# pneu-sensor.net
KiCad netlist of a schematic drawn in EAGLE
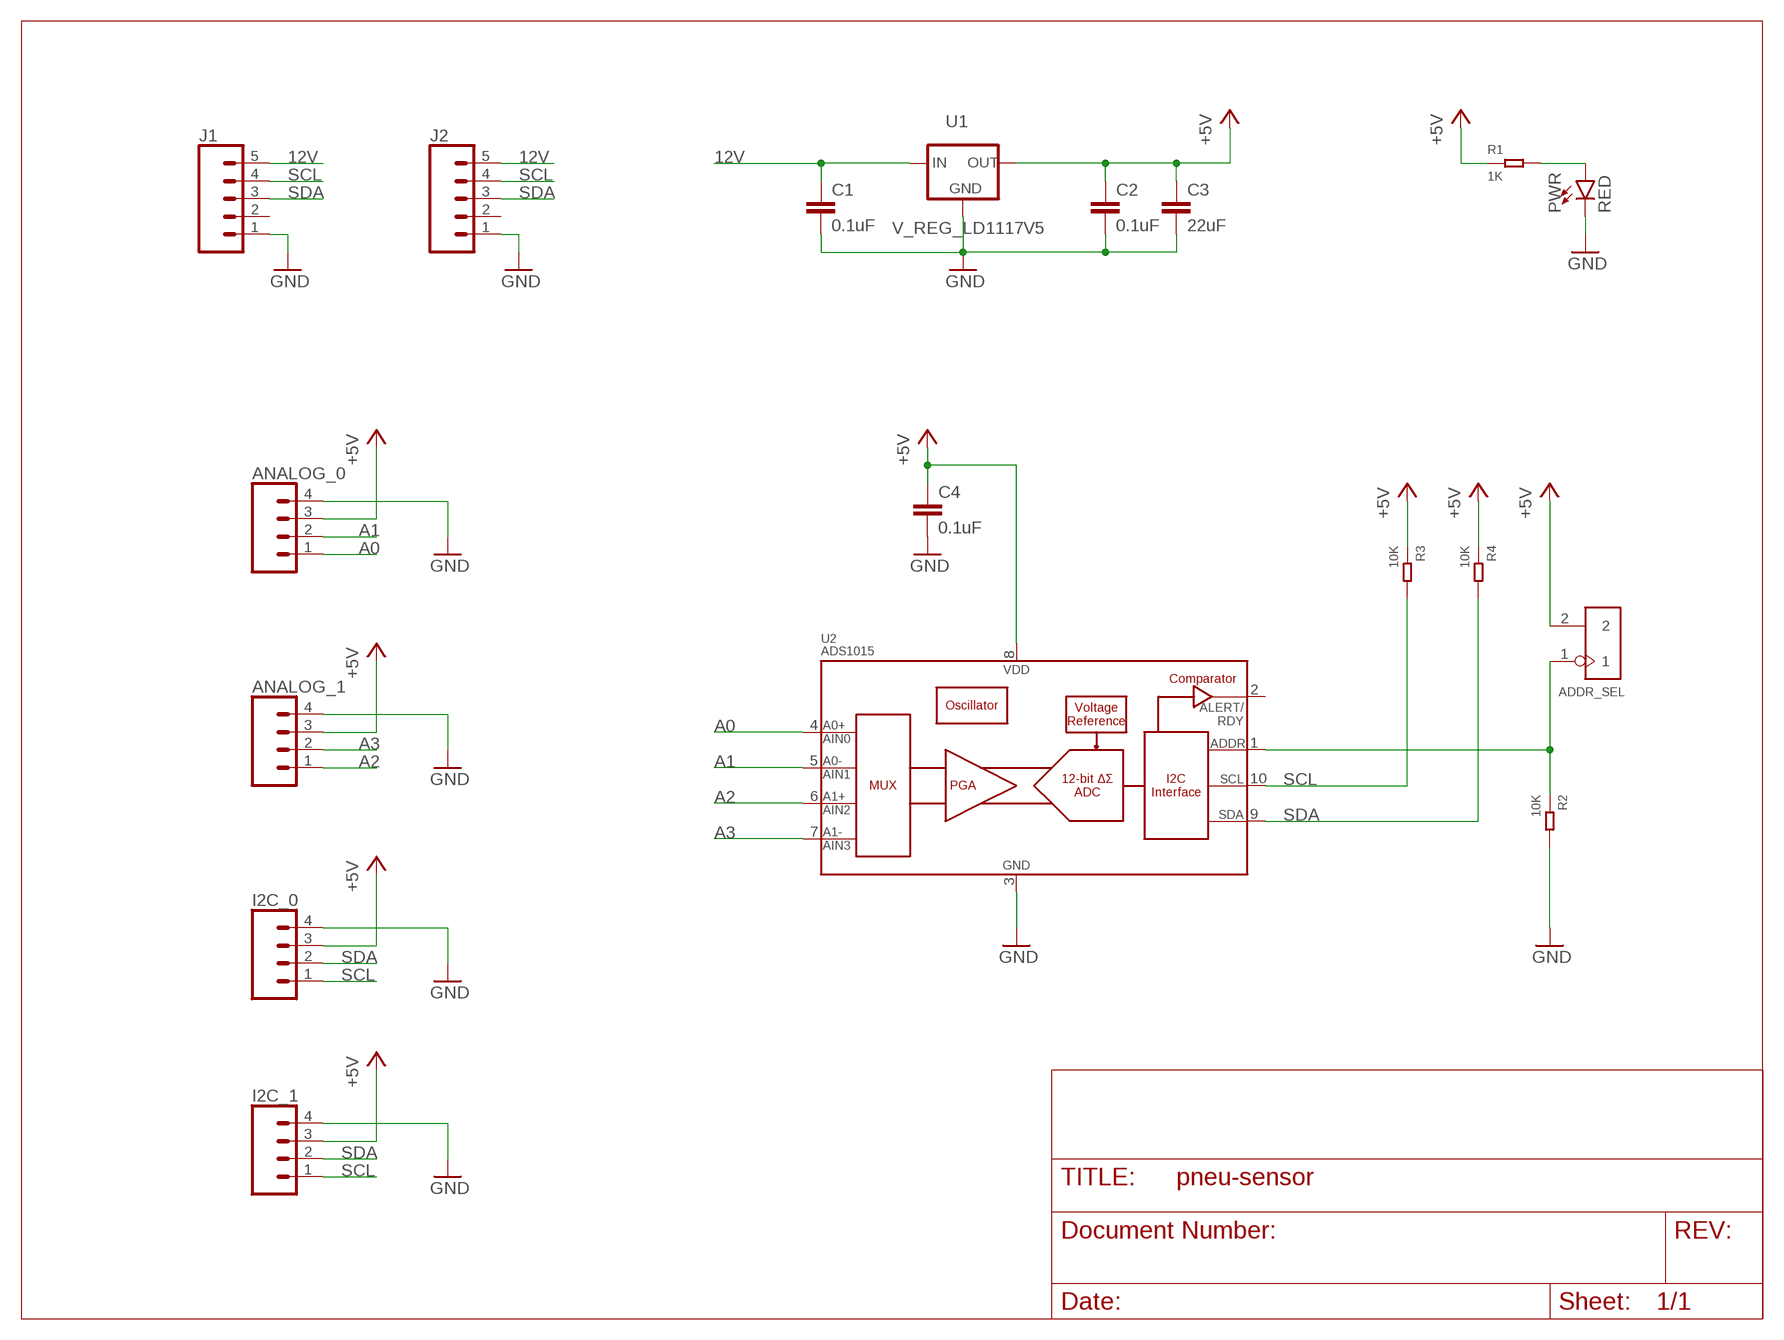
[diagram p0: schematic, sheet 1]

(export (version "E")
  (design (tool "Eeschema 10.0.6"))
  (components
    (comp (ref "ADDR_SEL")
      (value "DIP-BLACK-JUMPER")
      (footprint "eagle-import:H2-2.54")
      (libsource (lib "eagle-import") (part "DIP-BLACK-JUMPER"))
    )
    (comp (ref "ANALOG_0")
      (value "CONN_04JST-PTH-VERT")
      (footprint "eagle-import:JST-4-PTH-VERT")
      (libsource (lib "eagle-import") (part "CONN_04JST-PTH-VERT"))
    )
    (comp (ref "ANALOG_1")
      (value "CONN_04JST-PTH-VERT")
      (footprint "eagle-import:JST-4-PTH-VERT")
      (libsource (lib "eagle-import") (part "CONN_04JST-PTH-VERT"))
    )
    (comp (ref "C1")
      (value "0.1uF")
      (footprint "eagle-import:0603")
      (libsource (lib "eagle-import") (part "0.1UF-0603-25V-(+80/-20%)"))
    )
    (comp (ref "C2")
      (value "0.1uF")
      (footprint "eagle-import:0603")
      (libsource (lib "eagle-import") (part "0.1UF-0603-25V-(+80/-20%)"))
    )
    (comp (ref "C3")
      (value "22uF")
      (footprint "eagle-import:1206")
      (libsource (lib "eagle-import") (part "10UF-1206-6.3V-20%"))
    )
    (comp (ref "C4")
      (value "0.1uF")
      (footprint "eagle-import:0603")
      (libsource (lib "eagle-import") (part "0.1UF-0603-25V-(+80/-20%)"))
    )
    (comp (ref "I2C_0")
      (value "CONN_04JST-PTH-VERT")
      (footprint "eagle-import:JST-4-PTH-VERT")
      (libsource (lib "eagle-import") (part "CONN_04JST-PTH-VERT"))
    )
    (comp (ref "I2C_1")
      (value "CONN_04JST-PTH-VERT")
      (footprint "eagle-import:JST-4-PTH-VERT")
      (libsource (lib "eagle-import") (part "CONN_04JST-PTH-VERT"))
    )
    (comp (ref "J1")
      (value "CONN_05")
      (footprint "eagle-import:1X05")
      (libsource (lib "eagle-import") (part "CONN_05"))
    )
    (comp (ref "J2")
      (value "CONN_05")
      (footprint "eagle-import:1X05")
      (libsource (lib "eagle-import") (part "CONN_05"))
    )
    (comp (ref "PWR")
      (value "RED")
      (footprint "eagle-import:LED-0603")
      (libsource (lib "eagle-import") (part "LED-RED0603"))
    )
    (comp (ref "R1")
      (value "1K")
      (footprint "eagle-import:R0805")
      (fields (field (name "MPN") "RC0805JR-071KL"))
      (libsource (lib "eagle-import") (part "SMD-RES-1K-5%-1/8W(0805)"))
    )
    (comp (ref "R2")
      (value "10K")
      (footprint "eagle-import:R0805")
      (fields (field (name "MPN") "RC0805FR-0710KL"))
      (libsource (lib "eagle-import") (part "SMD-RES-10K-1%-1/8W(0805)"))
    )
    (comp (ref "R3")
      (value "10K")
      (footprint "eagle-import:R0805")
      (fields (field (name "MPN") "RC0805FR-0710KL"))
      (libsource (lib "eagle-import") (part "SMD-RES-10K-1%-1/8W(0805)"))
    )
    (comp (ref "R4")
      (value "10K")
      (footprint "eagle-import:R0805")
      (fields (field (name "MPN") "RC0805FR-0710KL"))
      (libsource (lib "eagle-import") (part "SMD-RES-10K-1%-1/8W(0805)"))
    )
    (comp (ref "U1")
      (value "V_REG_LD1117V5")
      (footprint "eagle-import:SOT223")
      (libsource (lib "eagle-import") (part "V_REG_LD1117VXXLD1117-SMD"))
    )
    (comp (ref "U2")
      (value "ADS1015")
      (footprint "eagle-import:MSOP10")
      (libsource (lib "eagle-import") (part "ADS1015"))
    )
  )
  (nets
    (net (code "1") (name "+5V") (class "Default")
      (node (ref "ADDR_SEL") (pin "2") (pinfunction "2_2") (pintype "bidirectional"))
      (node (ref "ANALOG_0") (pin "3") (pinfunction "3_3") (pintype "passive"))
      (node (ref "ANALOG_1") (pin "3") (pinfunction "3_3") (pintype "passive"))
      (node (ref "C2") (pin "1") (pinfunction "1_1") (pintype "passive"))
      (node (ref "C3") (pin "1") (pinfunction "1_1") (pintype "passive"))
      (node (ref "C4") (pin "1") (pinfunction "1_1") (pintype "passive"))
      (node (ref "I2C_0") (pin "3") (pinfunction "3_3") (pintype "passive"))
      (node (ref "I2C_1") (pin "3") (pinfunction "3_3") (pintype "passive"))
      (node (ref "R1") (pin "1") (pinfunction "1_1") (pintype "passive"))
      (node (ref "R3") (pin "1") (pinfunction "1_1") (pintype "passive"))
      (node (ref "R4") (pin "1") (pinfunction "1_1") (pintype "passive"))
      (node (ref "U1") (pin "2") (pinfunction "OUT_2") (pintype "passive"))
      (node (ref "U1") (pin "4") (pinfunction "OUT_4") (pintype "passive"))
      (node (ref "U2") (pin "8") (pinfunction "VDD_8") (pintype "bidirectional"))
    )
    (net (code "2") (name "/12V") (class "Default")
      (node (ref "C1") (pin "1") (pinfunction "1_1") (pintype "passive"))
      (node (ref "J1") (pin "5") (pinfunction "5_5") (pintype "passive"))
      (node (ref "J2") (pin "5") (pinfunction "5_5") (pintype "passive"))
      (node (ref "U1") (pin "3") (pinfunction "IN_3") (pintype "input"))
    )
    (net (code "3") (name "/A0") (class "Default")
      (node (ref "ANALOG_0") (pin "1") (pinfunction "1_1") (pintype "passive"))
      (node (ref "U2") (pin "4") (pinfunction "AIN0_4") (pintype "bidirectional"))
    )
    (net (code "4") (name "/A1") (class "Default")
      (node (ref "ANALOG_0") (pin "2") (pinfunction "2_2") (pintype "passive"))
      (node (ref "U2") (pin "5") (pinfunction "AIN1_5") (pintype "bidirectional"))
    )
    (net (code "5") (name "/A2") (class "Default")
      (node (ref "ANALOG_1") (pin "1") (pinfunction "1_1") (pintype "passive"))
      (node (ref "U2") (pin "6") (pinfunction "AIN2_6") (pintype "bidirectional"))
    )
    (net (code "6") (name "/A3") (class "Default")
      (node (ref "ANALOG_1") (pin "2") (pinfunction "2_2") (pintype "passive"))
      (node (ref "U2") (pin "7") (pinfunction "AIN3_7") (pintype "bidirectional"))
    )
    (net (code "7") (name "/SCL") (class "Default")
      (node (ref "I2C_0") (pin "1") (pinfunction "1_1") (pintype "passive"))
      (node (ref "I2C_1") (pin "1") (pinfunction "1_1") (pintype "passive"))
      (node (ref "J1") (pin "4") (pinfunction "4_4") (pintype "passive"))
      (node (ref "J2") (pin "4") (pinfunction "4_4") (pintype "passive"))
      (node (ref "R3") (pin "2") (pinfunction "2_2") (pintype "passive"))
      (node (ref "U2") (pin "10") (pinfunction "SCL_10") (pintype "bidirectional"))
    )
    (net (code "8") (name "/SDA") (class "Default")
      (node (ref "I2C_0") (pin "2") (pinfunction "2_2") (pintype "passive"))
      (node (ref "I2C_1") (pin "2") (pinfunction "2_2") (pintype "passive"))
      (node (ref "J1") (pin "3") (pinfunction "3_3") (pintype "passive"))
      (node (ref "J2") (pin "3") (pinfunction "3_3") (pintype "passive"))
      (node (ref "R4") (pin "2") (pinfunction "2_2") (pintype "passive"))
      (node (ref "U2") (pin "9") (pinfunction "SDA_9") (pintype "bidirectional"))
    )
    (net (code "9") (name "GND") (class "Default")
      (node (ref "ANALOG_0") (pin "4") (pinfunction "4_4") (pintype "passive"))
      (node (ref "ANALOG_1") (pin "4") (pinfunction "4_4") (pintype "passive"))
      (node (ref "C1") (pin "2") (pinfunction "2_2") (pintype "passive"))
      (node (ref "C2") (pin "2") (pinfunction "2_2") (pintype "passive"))
      (node (ref "C3") (pin "2") (pinfunction "2_2") (pintype "passive"))
      (node (ref "C4") (pin "2") (pinfunction "2_2") (pintype "passive"))
      (node (ref "I2C_0") (pin "4") (pinfunction "4_4") (pintype "passive"))
      (node (ref "I2C_1") (pin "4") (pinfunction "4_4") (pintype "passive"))
      (node (ref "J1") (pin "1") (pinfunction "1_1") (pintype "passive"))
      (node (ref "J2") (pin "1") (pinfunction "1_1") (pintype "passive"))
      (node (ref "PWR") (pin "C") (pinfunction "C_C") (pintype "passive"))
      (node (ref "R2") (pin "2") (pinfunction "2_2") (pintype "passive"))
      (node (ref "U1") (pin "1") (pinfunction "GND_1") (pintype "input"))
      (node (ref "U2") (pin "3") (pinfunction "VSS_3") (pintype "bidirectional"))
    )
    (net (code "10") (name "Net-(PWR-PadA)") (class "Default")
      (node (ref "PWR") (pin "A") (pinfunction "A_A") (pintype "passive"))
      (node (ref "R1") (pin "2") (pinfunction "2_2") (pintype "passive"))
    )
    (net (code "11") (name "Net-(U2-ADDR)") (class "Default")
      (node (ref "ADDR_SEL") (pin "1") (pinfunction "1_1") (pintype "bidirectional"))
      (node (ref "R2") (pin "1") (pinfunction "1_1") (pintype "passive"))
      (node (ref "U2") (pin "1") (pinfunction "ADDR_1") (pintype "bidirectional"))
    )
    (net (code "12") (name "unconnected-(J1-Pad2)") (class "Default")
      (node (ref "J1") (pin "2") (pinfunction "2_2") (pintype "passive"))
    )
    (net (code "13") (name "unconnected-(J2-Pad2)") (class "Default")
      (node (ref "J2") (pin "2") (pinfunction "2_2") (pintype "passive"))
    )
    (net (code "14") (name "unconnected-(U2-ALERT{slash}RDY-Pad2)") (class "Default")
      (node (ref "U2") (pin "2") (pinfunction "ALERT/RDY_2") (pintype "bidirectional"))
    )
  )
)
